# switcher-3A.net
KiCad netlist of a schematic drawn in Altium Designer
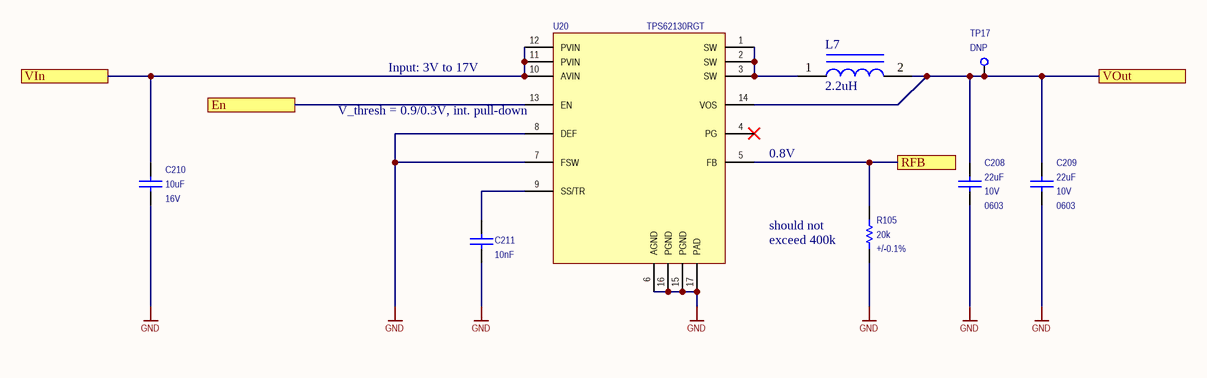
[diagram p0: switcher-3A.SchDoc]

(export (version "E")
  (design (tool "Eeschema 10.0.6"))
  (components
    (comp (ref "C208")
      (value "22uF")
      (footprint "0603")
      (description "Ceramic Capacitor 22uF +/-20% 10V X5R SMD 0603")
      (fields
        (field (name "MANUFACTURER") "TDK Corporation")
        (field (name "TOLERANCE") "+/-20%")
        (field (name "VOLTAGE") "10V")
      )
      (libsource (lib "generic") (part "CAP"))
    )
    (comp (ref "C209")
      (value "22uF")
      (footprint "0603")
      (description "Ceramic Capacitor 22uF +/-20% 10V X5R SMD 0603")
      (fields
        (field (name "MANUFACTURER") "TDK Corporation")
        (field (name "TOLERANCE") "+/-20%")
        (field (name "VOLTAGE") "10V")
      )
      (libsource (lib "generic") (part "CAP"))
    )
    (comp (ref "C210")
      (value "10uF")
      (footprint "0603")
      (description "Ceramic Capacitor 10uF +/-20% 16V X5R 0603")
      (fields
        (field (name "MANUFACTURER") "Taiyo Yuden")
        (field (name "VOLTAGE") "16V")
        (field (name "Comment") "CAP 10UF 0603")
      )
      (libsource (lib "") (part "CAP_1"))
    )
    (comp (ref "C211")
      (value "10nF")
      (footprint "0201")
      (description "Ceramic Capacitor 10nF +/-10% 10V X5R 0201")
      (fields (field (name "MANUFACTURER") "TDK Corporation") (field (name "VOLTAGE") "10V"))
      (libsource (lib "") (part "CAP_1"))
    )
    (comp (ref "L7")
      (value "2.2uH")
      (footprint "SRP4020")
      (description "Ind 2.2uH 4A SRP4020")
      (fields (field (name "MFG") "Bourns"))
      (libsource (lib "Kron Library Rev 3") (part "SRP4020TA-2R2M"))
    )
    (comp (ref "R105")
      (value "20k")
      (footprint "RESC1608X55N")
      (description "Thick Film Resistor 20k Ohms +/-0.1% 0.1W 75V SMD 0603")
      (fields
        (field (name "TOLERANCE") "+/-0.1%")
        (field (name "MANUFACTURER") "Panasonic - ECG")
        (field (name "VOLTAGE") "75V")
      )
      (libsource (lib "brinton") (part "RES"))
    )
    (comp (ref "TP17")
      (value "TEST_POINT")
      (footprint "TEST_POINT")
      (description "Thruhole Miniature Test Point")
      (fields (field (name "MANUFACTURER") "Keystone Electronics Corp") (field (name "DO NOT PLACE") "DNP"))
      (libsource (lib "generic") (part "TEST_POINT"))
    )
    (comp (ref "U20")
      (value "TPS62130RGT")
      (footprint "S-PQFP-8N")
      (description "3-17V 3A Step-Down Converter VQFN")
      (fields (field (name "MANUFACTURER") "Texas Instruments"))
      (libsource (lib "ti") (part "TPS62130RGT"))
    )
  )
  (nets
    (net (code "1") (name "/En") (class "Default")
      (node (ref "U20") (pin "13") (pinfunction "EN_13") (pintype "passive"))
    )
    (net (code "2") (name "/RFB") (class "Default")
      (node (ref "R105") (pin "2") (pinfunction "2_2") (pintype "passive"))
      (node (ref "U20") (pin "5") (pinfunction "FB_5") (pintype "passive"))
    )
    (net (code "3") (name "/VIn") (class "Default")
      (node (ref "C210") (pin "2") (pinfunction "2_2") (pintype "passive"))
      (node (ref "U20") (pin "10") (pinfunction "AVIN_10") (pintype "passive"))
      (node (ref "U20") (pin "11") (pinfunction "PVIN_11") (pintype "passive"))
      (node (ref "U20") (pin "12") (pinfunction "PVIN_12") (pintype "passive"))
    )
    (net (code "4") (name "/VOut") (class "Default")
      (node (ref "C208") (pin "2") (pinfunction "2_2") (pintype "passive"))
      (node (ref "C209") (pin "2") (pinfunction "2_2") (pintype "passive"))
      (node (ref "L7") (pin "2") (pintype "passive"))
      (node (ref "TP17") (pin "1") (pinfunction "1_1") (pintype "passive"))
      (node (ref "U20") (pin "14") (pinfunction "VOS_14") (pintype "passive"))
    )
    (net (code "5") (name "GND") (class "Default")
      (node (ref "C208") (pin "1") (pinfunction "1_1") (pintype "passive"))
      (node (ref "C209") (pin "1") (pinfunction "1_1") (pintype "passive"))
      (node (ref "C210") (pin "1") (pinfunction "1_1") (pintype "passive"))
      (node (ref "C211") (pin "2") (pinfunction "2_2") (pintype "passive"))
      (node (ref "R105") (pin "1") (pinfunction "1_1") (pintype "passive"))
      (node (ref "U20") (pin "15") (pinfunction "PGND_15") (pintype "passive"))
      (node (ref "U20") (pin "16") (pinfunction "PGND_16") (pintype "passive"))
      (node (ref "U20") (pin "17") (pinfunction "PAD_17") (pintype "passive"))
      (node (ref "U20") (pin "6") (pinfunction "AGND_6") (pintype "passive"))
      (node (ref "U20") (pin "7") (pinfunction "FSW_7") (pintype "passive"))
      (node (ref "U20") (pin "8") (pinfunction "DEF_8") (pintype "passive"))
    )
    (net (code "6") (name "Net-(L7-Pad1)") (class "Default")
      (node (ref "L7") (pin "1") (pintype "passive"))
      (node (ref "U20") (pin "1") (pinfunction "SW_1") (pintype "passive"))
      (node (ref "U20") (pin "2") (pinfunction "SW_2") (pintype "passive"))
      (node (ref "U20") (pin "3") (pinfunction "SW_3") (pintype "passive"))
    )
    (net (code "7") (name "Net-(U20-SS{slash}TR)") (class "Default")
      (node (ref "C211") (pin "1") (pinfunction "1_1") (pintype "passive"))
      (node (ref "U20") (pin "9") (pinfunction "SS/TR_9") (pintype "passive"))
    )
    (net (code "8") (name "unconnected-(U20-PG-Pad4)") (class "Default")
      (node (ref "U20") (pin "4") (pinfunction "PG_4") (pintype "passive+no_connect"))
    )
  )
)
